# Stoplight.net
KiCad netlist of a schematic drawn in EAGLE
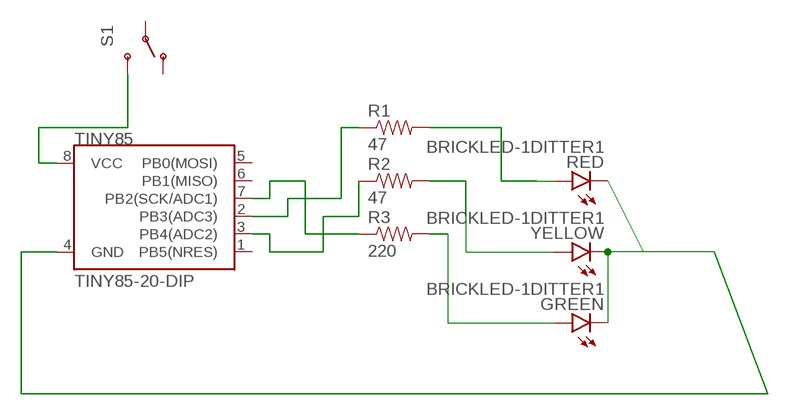
[diagram p0: schematic, sheet 1]

(export (version "E")
  (design (tool "Eeschema 10.0.6"))
  (components
    (comp (ref "GREEN")
      (value "BRICKLED-1DITTER1")
      (footprint "eagle-import:BRICKLED-1DITTER")
      (libsource (lib "eagle-import") (part "BRICKLED-1DITTER1"))
    )
    (comp (ref "R1")
      (value "47")
      (footprint "eagle-import:AXIAL-0.3")
      (libsource (lib "eagle-import") (part "10KOHM-1/4W5%(PTH)"))
    )
    (comp (ref "R2")
      (value "47")
      (footprint "eagle-import:AXIAL-0.3")
      (libsource (lib "eagle-import") (part "10KOHM-1/4W5%(PTH)"))
    )
    (comp (ref "R3")
      (value "220")
      (footprint "eagle-import:AXIAL-0.3")
      (libsource (lib "eagle-import") (part "10KOHM-1/4W5%(PTH)"))
    )
    (comp (ref "RED")
      (value "BRICKLED-1DITTER1")
      (footprint "eagle-import:BRICKLED-1DITTER")
      (libsource (lib "eagle-import") (part "BRICKLED-1DITTER1"))
    )
    (comp (ref "S1")
      (value "SWITCH-SPDTKIT")
      (footprint "eagle-import:SWITCH-SPDT_KIT")
      (libsource (lib "eagle-import") (part "SWITCH-SPDTKIT"))
    )
    (comp (ref "TINY85")
      (value "TINY85-20-DIP")
      (footprint "eagle-import:DIP08")
      (libsource (lib "eagle-import") (part "ATTINY45TINY85-20-DIP"))
    )
    (comp (ref "YELLOW")
      (value "BRICKLED-1DITTER1")
      (footprint "eagle-import:BRICKLED-1DITTER")
      (libsource (lib "eagle-import") (part "BRICKLED-1DITTER1"))
    )
  )
  (nets
    (net (code "1") (name "Net-(GREEN-C)") (class "Default")
      (node (ref "GREEN") (pin "K") (pinfunction "C_K") (pintype "passive"))
      (node (ref "RED") (pin "K") (pinfunction "C_K") (pintype "passive"))
      (node (ref "TINY85") (pin "4") (pinfunction "GND_4") (pintype "bidirectional"))
      (node (ref "YELLOW") (pin "K") (pinfunction "C_K") (pintype "passive"))
    )
    (net (code "2") (name "Net-(R1-1)") (class "Default")
      (node (ref "R1") (pin "P$1") (pinfunction "1_P$1") (pintype "passive"))
      (node (ref "TINY85") (pin "2") (pinfunction "PB3(ADC3)_2") (pintype "bidirectional"))
    )
    (net (code "3") (name "Net-(R1-2)") (class "Default")
      (node (ref "R1") (pin "P$2") (pinfunction "2_P$2") (pintype "passive"))
      (node (ref "RED") (pin "A") (pinfunction "A_A") (pintype "passive"))
    )
    (net (code "4") (name "Net-(R2-1)") (class "Default")
      (node (ref "R2") (pin "P$1") (pinfunction "1_P$1") (pintype "passive"))
      (node (ref "TINY85") (pin "3") (pinfunction "PB4(ADC2)_3") (pintype "bidirectional"))
    )
    (net (code "5") (name "Net-(R2-2)") (class "Default")
      (node (ref "R2") (pin "P$2") (pinfunction "2_P$2") (pintype "passive"))
      (node (ref "YELLOW") (pin "A") (pinfunction "A_A") (pintype "passive"))
    )
    (net (code "6") (name "Net-(R3-1)") (class "Default")
      (node (ref "R3") (pin "P$1") (pinfunction "1_P$1") (pintype "passive"))
      (node (ref "TINY85") (pin "7") (pinfunction "PB2(SCK/ADC1)_7") (pintype "bidirectional"))
    )
    (net (code "7") (name "Net-(R3-2)") (class "Default")
      (node (ref "GREEN") (pin "A") (pinfunction "A_A") (pintype "passive"))
      (node (ref "R3") (pin "P$2") (pinfunction "2_P$2") (pintype "passive"))
    )
    (net (code "8") (name "Net-(S1-S)") (class "Default")
      (node (ref "S1") (pin "3") (pinfunction "S_3") (pintype "passive"))
      (node (ref "TINY85") (pin "8") (pinfunction "VCC_8") (pintype "bidirectional"))
    )
    (net (code "9") (name "unconnected-(S1-O-Pad1)") (class "Default")
      (node (ref "S1") (pin "1") (pinfunction "O_1") (pintype "passive"))
    )
    (net (code "10") (name "unconnected-(S1-P-Pad2)") (class "Default")
      (node (ref "S1") (pin "2") (pinfunction "P_2") (pintype "passive"))
    )
    (net (code "11") (name "unconnected-(TINY85-PB0(MOSI)-Pad5)") (class "Default")
      (node (ref "TINY85") (pin "5") (pinfunction "PB0(MOSI)_5") (pintype "bidirectional"))
    )
    (net (code "12") (name "unconnected-(TINY85-PB1(MISO)-Pad6)") (class "Default")
      (node (ref "TINY85") (pin "6") (pinfunction "PB1(MISO)_6") (pintype "bidirectional"))
    )
    (net (code "13") (name "unconnected-(TINY85-PB5(NRES)-Pad1)") (class "Default")
      (node (ref "TINY85") (pin "1") (pinfunction "PB5(NRES)_1") (pintype "bidirectional"))
    )
  )
)
